# AMP_OP1.net
KiCad netlist of a schematic drawn in EAGLE
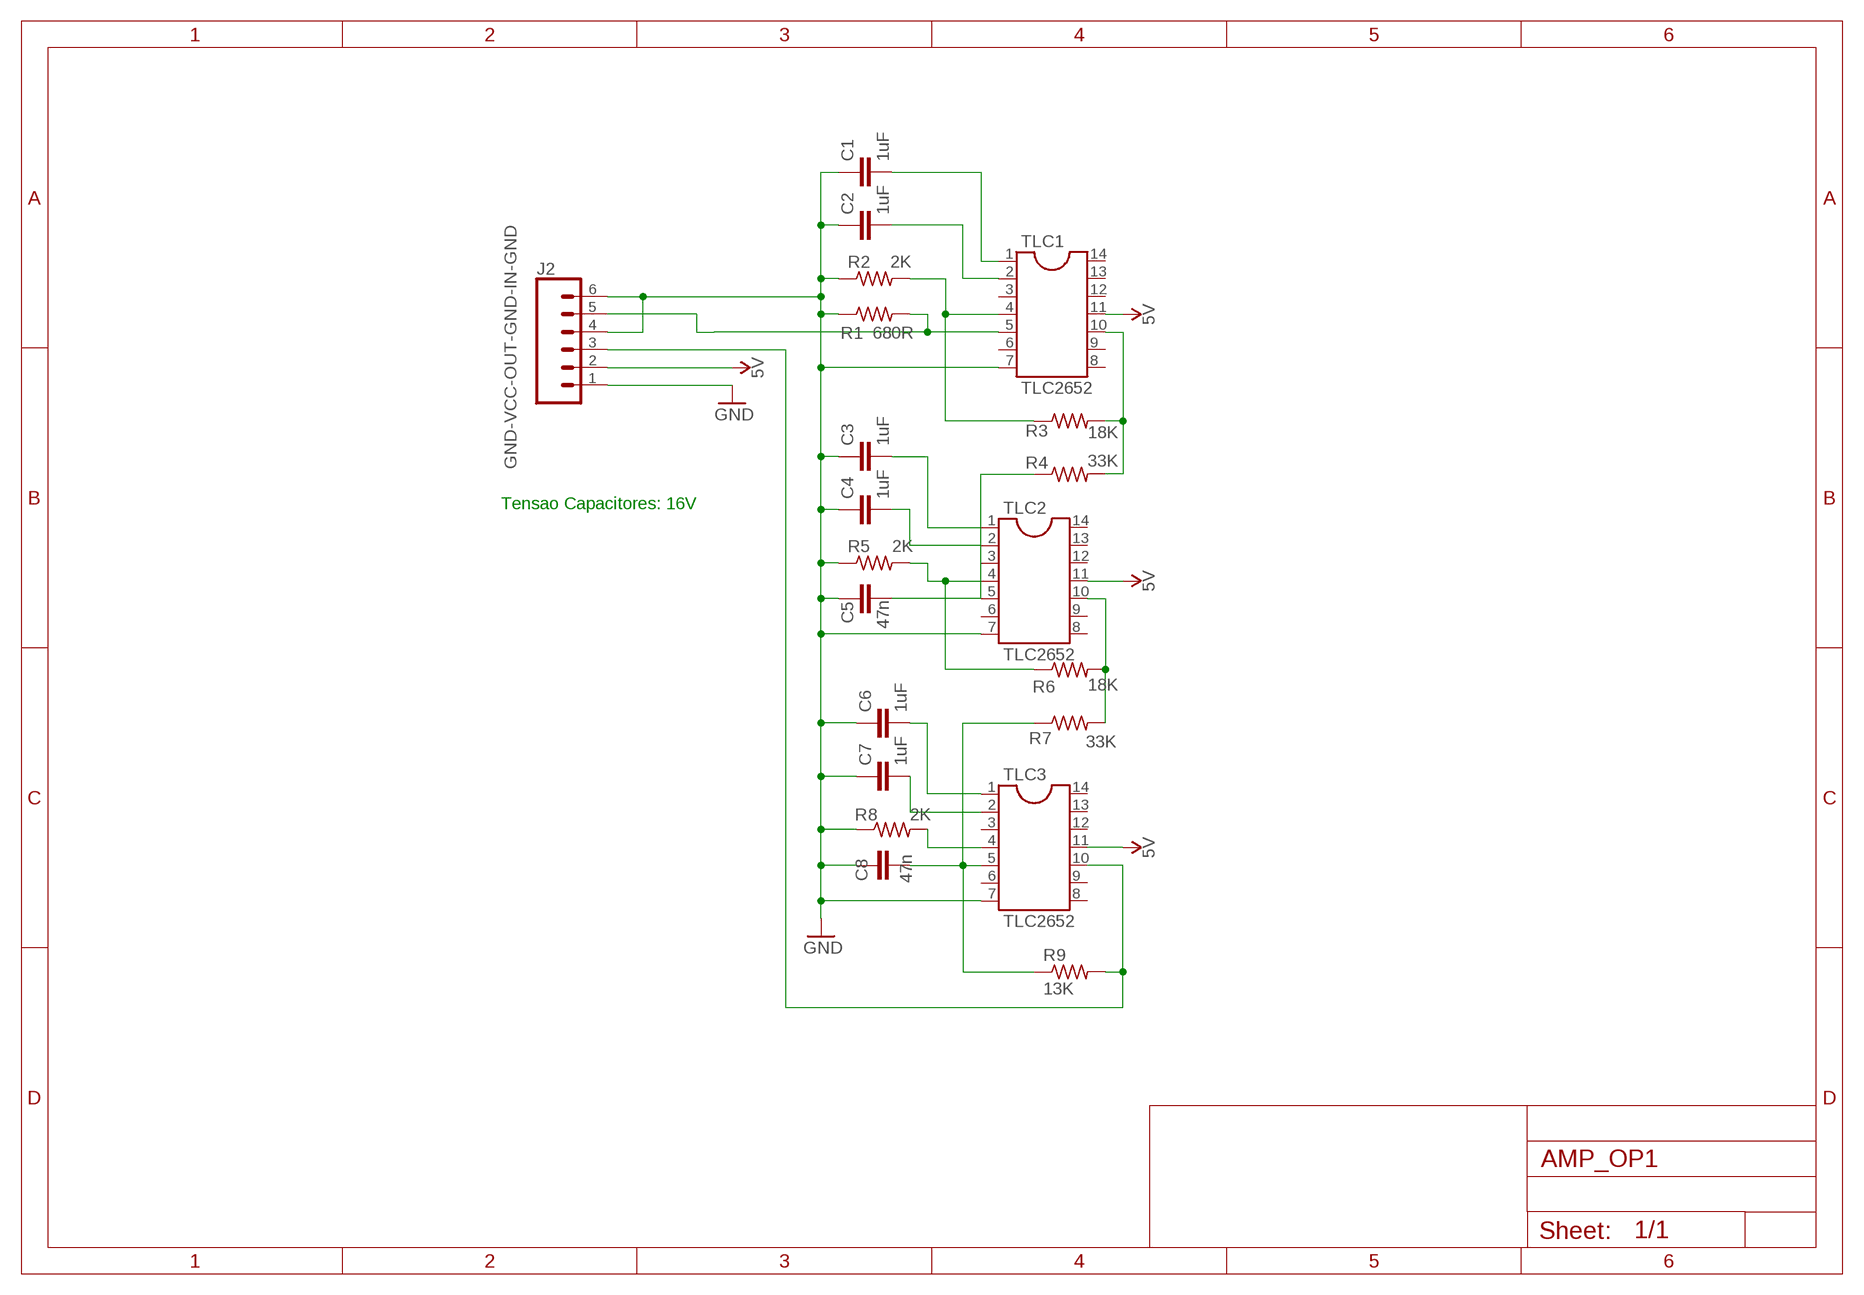
[diagram p0: schematic, sheet 1]

(export (version "E")
  (design (tool "Eeschema 10.0.6"))
  (components
    (comp (ref "C1")
      (value "1uF")
      (footprint "eagle-import:C5B3.5")
      (libsource (lib "eagle-import") (part "C5/3.5"))
    )
    (comp (ref "C2")
      (value "1uF")
      (footprint "eagle-import:C5B3.5")
      (libsource (lib "eagle-import") (part "C5/3.5"))
    )
    (comp (ref "C3")
      (value "1uF")
      (footprint "eagle-import:C5B3.5")
      (libsource (lib "eagle-import") (part "C5/3.5"))
    )
    (comp (ref "C4")
      (value "1uF")
      (footprint "eagle-import:C5B3.5")
      (libsource (lib "eagle-import") (part "C5/3.5"))
    )
    (comp (ref "C5")
      (value "47n")
      (footprint "eagle-import:C5B3.5")
      (libsource (lib "eagle-import") (part "C5/3.5"))
    )
    (comp (ref "C6")
      (value "1uF")
      (footprint "eagle-import:C5B3.5")
      (libsource (lib "eagle-import") (part "C5/3.5"))
    )
    (comp (ref "C7")
      (value "1uF")
      (footprint "eagle-import:C5B3.5")
      (libsource (lib "eagle-import") (part "C5/3.5"))
    )
    (comp (ref "C8")
      (value "47n")
      (footprint "eagle-import:C5B3.5")
      (libsource (lib "eagle-import") (part "C5/3.5"))
    )
    (comp (ref "J2")
      (value "GND-VCC-OUT-GND-IN-GND")
      (footprint "eagle-import:1X06_LONGPADS")
      (libsource (lib "eagle-import") (part "CONN_06LONGPADS"))
    )
    (comp (ref "R1")
      (value "680R")
      (footprint "eagle-import:0207_9")
      (libsource (lib "eagle-import") (part "R-US_0207/9"))
    )
    (comp (ref "R2")
      (value "2K")
      (footprint "eagle-import:0207_9")
      (libsource (lib "eagle-import") (part "R-US_0207/9"))
    )
    (comp (ref "R3")
      (value "18K")
      (footprint "eagle-import:0207_9")
      (libsource (lib "eagle-import") (part "R-US_0207/9"))
    )
    (comp (ref "R4")
      (value "33K")
      (footprint "eagle-import:0207_9")
      (libsource (lib "eagle-import") (part "R-US_0207/9"))
    )
    (comp (ref "R5")
      (value "2K")
      (footprint "eagle-import:0207_9")
      (libsource (lib "eagle-import") (part "R-US_0207/9"))
    )
    (comp (ref "R6")
      (value "18K")
      (footprint "eagle-import:0207_9")
      (libsource (lib "eagle-import") (part "R-US_0207/9"))
    )
    (comp (ref "R7")
      (value "33K")
      (footprint "eagle-import:0207_9")
      (libsource (lib "eagle-import") (part "R-US_0207/9"))
    )
    (comp (ref "R8")
      (value "2K")
      (footprint "eagle-import:0207_9")
      (libsource (lib "eagle-import") (part "R-US_0207/9"))
    )
    (comp (ref "R9")
      (value "13K")
      (footprint "eagle-import:0207_9")
      (libsource (lib "eagle-import") (part "R-US_0207/9"))
    )
    (comp (ref "TLC1")
      (value "TLC2652")
      (footprint "eagle-import:DIL14")
      (libsource (lib "eagle-import") (part "DIL14"))
    )
    (comp (ref "TLC2")
      (value "TLC2652")
      (footprint "eagle-import:DIL14")
      (libsource (lib "eagle-import") (part "DIL14"))
    )
    (comp (ref "TLC3")
      (value "TLC2652")
      (footprint "eagle-import:DIL14")
      (libsource (lib "eagle-import") (part "DIL14"))
    )
  )
  (nets
    (net (code "1") (name "5V") (class "Default")
      (node (ref "J2") (pin "2") (pinfunction "2_2") (pintype "passive"))
      (node (ref "TLC1") (pin "11") (pinfunction "11_11") (pintype "passive"))
      (node (ref "TLC2") (pin "11") (pinfunction "11_11") (pintype "passive"))
      (node (ref "TLC3") (pin "11") (pinfunction "11_11") (pintype "passive"))
    )
    (net (code "2") (name "GND") (class "Default")
      (node (ref "C1") (pin "1") (pinfunction "1_1") (pintype "passive"))
      (node (ref "C2") (pin "1") (pinfunction "1_1") (pintype "passive"))
      (node (ref "C3") (pin "1") (pinfunction "1_1") (pintype "passive"))
      (node (ref "C4") (pin "1") (pinfunction "1_1") (pintype "passive"))
      (node (ref "C5") (pin "1") (pinfunction "1_1") (pintype "passive"))
      (node (ref "C6") (pin "1") (pinfunction "1_1") (pintype "passive"))
      (node (ref "C7") (pin "1") (pinfunction "1_1") (pintype "passive"))
      (node (ref "C8") (pin "1") (pinfunction "1_1") (pintype "passive"))
      (node (ref "J2") (pin "1") (pinfunction "1_1") (pintype "passive"))
      (node (ref "J2") (pin "4") (pinfunction "4_4") (pintype "passive"))
      (node (ref "J2") (pin "6") (pinfunction "6_6") (pintype "passive"))
      (node (ref "R1") (pin "1") (pinfunction "1_1") (pintype "passive"))
      (node (ref "R2") (pin "1") (pinfunction "1_1") (pintype "passive"))
      (node (ref "R5") (pin "1") (pinfunction "1_1") (pintype "passive"))
      (node (ref "R8") (pin "1") (pinfunction "1_1") (pintype "passive"))
      (node (ref "TLC1") (pin "7") (pinfunction "7_7") (pintype "passive"))
      (node (ref "TLC2") (pin "7") (pinfunction "7_7") (pintype "passive"))
      (node (ref "TLC3") (pin "7") (pinfunction "7_7") (pintype "passive"))
    )
    (net (code "3") (name "Net-(C1-Pad2)") (class "Default")
      (node (ref "C1") (pin "2") (pinfunction "2_2") (pintype "passive"))
      (node (ref "TLC1") (pin "1") (pinfunction "1_1") (pintype "passive"))
    )
    (net (code "4") (name "Net-(C2-Pad2)") (class "Default")
      (node (ref "C2") (pin "2") (pinfunction "2_2") (pintype "passive"))
      (node (ref "TLC1") (pin "2") (pinfunction "2_2") (pintype "passive"))
    )
    (net (code "5") (name "Net-(C3-Pad2)") (class "Default")
      (node (ref "C3") (pin "2") (pinfunction "2_2") (pintype "passive"))
      (node (ref "TLC2") (pin "1") (pinfunction "1_1") (pintype "passive"))
    )
    (net (code "6") (name "Net-(C4-Pad2)") (class "Default")
      (node (ref "C4") (pin "2") (pinfunction "2_2") (pintype "passive"))
      (node (ref "TLC2") (pin "2") (pinfunction "2_2") (pintype "passive"))
    )
    (net (code "7") (name "Net-(C5-Pad2)") (class "Default")
      (node (ref "C5") (pin "2") (pinfunction "2_2") (pintype "passive"))
      (node (ref "R4") (pin "1") (pinfunction "1_1") (pintype "passive"))
      (node (ref "TLC2") (pin "3") (pinfunction "3_3") (pintype "passive"))
      (node (ref "TLC2") (pin "5") (pinfunction "5_5") (pintype "passive"))
    )
    (net (code "8") (name "Net-(C6-Pad2)") (class "Default")
      (node (ref "C6") (pin "2") (pinfunction "2_2") (pintype "passive"))
      (node (ref "TLC3") (pin "1") (pinfunction "1_1") (pintype "passive"))
    )
    (net (code "9") (name "Net-(C7-Pad2)") (class "Default")
      (node (ref "C7") (pin "2") (pinfunction "2_2") (pintype "passive"))
      (node (ref "TLC3") (pin "2") (pinfunction "2_2") (pintype "passive"))
    )
    (net (code "10") (name "Net-(C8-Pad2)") (class "Default")
      (node (ref "C8") (pin "2") (pinfunction "2_2") (pintype "passive"))
      (node (ref "R7") (pin "1") (pinfunction "1_1") (pintype "passive"))
      (node (ref "R9") (pin "1") (pinfunction "1_1") (pintype "passive"))
      (node (ref "TLC3") (pin "5") (pinfunction "5_5") (pintype "passive"))
    )
    (net (code "11") (name "Net-(J2-Pad3)") (class "Default")
      (node (ref "J2") (pin "3") (pinfunction "3_3") (pintype "passive"))
      (node (ref "R9") (pin "2") (pinfunction "2_2") (pintype "passive"))
      (node (ref "TLC3") (pin "10") (pinfunction "10_10") (pintype "passive"))
    )
    (net (code "12") (name "Net-(J2-Pad5)") (class "Default")
      (node (ref "J2") (pin "5") (pinfunction "5_5") (pintype "passive"))
      (node (ref "R1") (pin "2") (pinfunction "2_2") (pintype "passive"))
      (node (ref "TLC1") (pin "5") (pinfunction "5_5") (pintype "passive"))
    )
    (net (code "13") (name "Net-(R2-Pad2)") (class "Default")
      (node (ref "R2") (pin "2") (pinfunction "2_2") (pintype "passive"))
      (node (ref "R3") (pin "1") (pinfunction "1_1") (pintype "passive"))
      (node (ref "TLC1") (pin "4") (pinfunction "4_4") (pintype "passive"))
    )
    (net (code "14") (name "Net-(R3-Pad2)") (class "Default")
      (node (ref "R3") (pin "2") (pinfunction "2_2") (pintype "passive"))
      (node (ref "R4") (pin "2") (pinfunction "2_2") (pintype "passive"))
      (node (ref "TLC1") (pin "10") (pinfunction "10_10") (pintype "passive"))
    )
    (net (code "15") (name "Net-(R5-Pad2)") (class "Default")
      (node (ref "R5") (pin "2") (pinfunction "2_2") (pintype "passive"))
      (node (ref "R6") (pin "1") (pinfunction "1_1") (pintype "passive"))
      (node (ref "TLC2") (pin "4") (pinfunction "4_4") (pintype "passive"))
    )
    (net (code "16") (name "Net-(R6-Pad2)") (class "Default")
      (node (ref "R6") (pin "2") (pinfunction "2_2") (pintype "passive"))
      (node (ref "R7") (pin "2") (pinfunction "2_2") (pintype "passive"))
      (node (ref "TLC2") (pin "10") (pinfunction "10_10") (pintype "passive"))
    )
    (net (code "17") (name "Net-(R8-Pad2)") (class "Default")
      (node (ref "R8") (pin "2") (pinfunction "2_2") (pintype "passive"))
      (node (ref "TLC3") (pin "4") (pinfunction "4_4") (pintype "passive"))
    )
    (net (code "18") (name "unconnected-(TLC1-Pad3)") (class "Default")
      (node (ref "TLC1") (pin "3") (pinfunction "3_3") (pintype "passive"))
    )
    (net (code "19") (name "unconnected-(TLC1-Pad6)") (class "Default")
      (node (ref "TLC1") (pin "6") (pinfunction "6_6") (pintype "passive"))
    )
    (net (code "20") (name "unconnected-(TLC1-Pad8)") (class "Default")
      (node (ref "TLC1") (pin "8") (pinfunction "8_8") (pintype "passive"))
    )
    (net (code "21") (name "unconnected-(TLC1-Pad9)") (class "Default")
      (node (ref "TLC1") (pin "9") (pinfunction "9_9") (pintype "passive"))
    )
    (net (code "22") (name "unconnected-(TLC1-Pad12)") (class "Default")
      (node (ref "TLC1") (pin "12") (pinfunction "12_12") (pintype "passive"))
    )
    (net (code "23") (name "unconnected-(TLC1-Pad13)") (class "Default")
      (node (ref "TLC1") (pin "13") (pinfunction "13_13") (pintype "passive"))
    )
    (net (code "24") (name "unconnected-(TLC1-Pad14)") (class "Default")
      (node (ref "TLC1") (pin "14") (pinfunction "14_14") (pintype "passive"))
    )
    (net (code "25") (name "unconnected-(TLC2-Pad6)") (class "Default")
      (node (ref "TLC2") (pin "6") (pinfunction "6_6") (pintype "passive"))
    )
    (net (code "26") (name "unconnected-(TLC2-Pad8)") (class "Default")
      (node (ref "TLC2") (pin "8") (pinfunction "8_8") (pintype "passive"))
    )
    (net (code "27") (name "unconnected-(TLC2-Pad9)") (class "Default")
      (node (ref "TLC2") (pin "9") (pinfunction "9_9") (pintype "passive"))
    )
    (net (code "28") (name "unconnected-(TLC2-Pad12)") (class "Default")
      (node (ref "TLC2") (pin "12") (pinfunction "12_12") (pintype "passive"))
    )
    (net (code "29") (name "unconnected-(TLC2-Pad13)") (class "Default")
      (node (ref "TLC2") (pin "13") (pinfunction "13_13") (pintype "passive"))
    )
    (net (code "30") (name "unconnected-(TLC2-Pad14)") (class "Default")
      (node (ref "TLC2") (pin "14") (pinfunction "14_14") (pintype "passive"))
    )
    (net (code "31") (name "unconnected-(TLC3-Pad3)") (class "Default")
      (node (ref "TLC3") (pin "3") (pinfunction "3_3") (pintype "passive"))
    )
    (net (code "32") (name "unconnected-(TLC3-Pad6)") (class "Default")
      (node (ref "TLC3") (pin "6") (pinfunction "6_6") (pintype "passive"))
    )
    (net (code "33") (name "unconnected-(TLC3-Pad8)") (class "Default")
      (node (ref "TLC3") (pin "8") (pinfunction "8_8") (pintype "passive"))
    )
    (net (code "34") (name "unconnected-(TLC3-Pad9)") (class "Default")
      (node (ref "TLC3") (pin "9") (pinfunction "9_9") (pintype "passive"))
    )
    (net (code "35") (name "unconnected-(TLC3-Pad12)") (class "Default")
      (node (ref "TLC3") (pin "12") (pinfunction "12_12") (pintype "passive"))
    )
    (net (code "36") (name "unconnected-(TLC3-Pad13)") (class "Default")
      (node (ref "TLC3") (pin "13") (pinfunction "13_13") (pintype "passive"))
    )
    (net (code "37") (name "unconnected-(TLC3-Pad14)") (class "Default")
      (node (ref "TLC3") (pin "14") (pinfunction "14_14") (pintype "passive"))
    )
  )
)
